# 12V_Regulator.net
KiCad netlist of a schematic drawn in Altium Designer
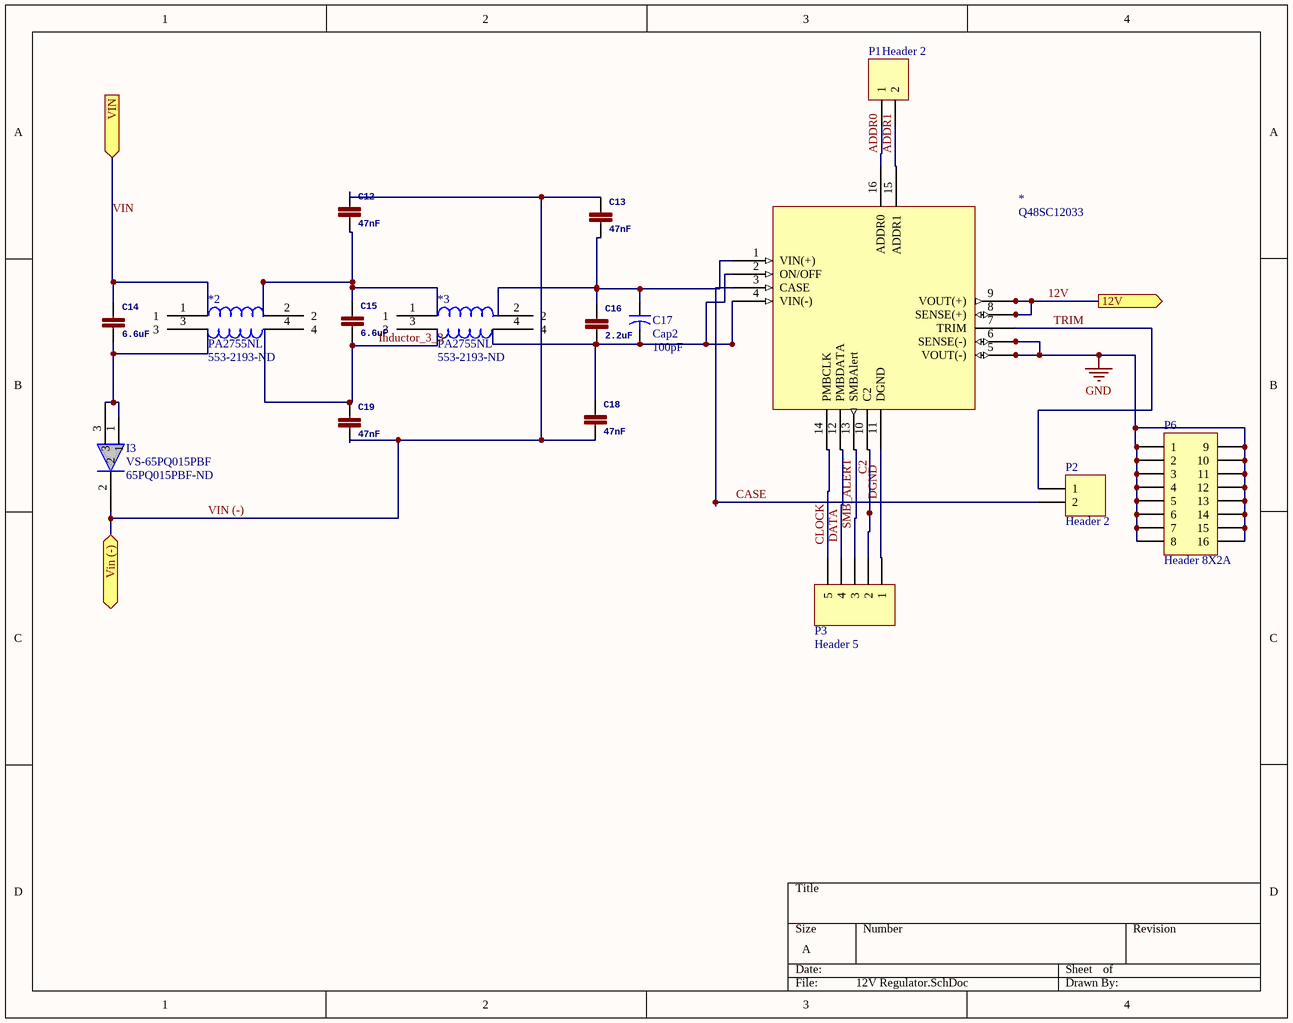
[diagram p0: 12V Regulator.SchDoc]

(export (version "E")
  (design (tool "Eeschema 10.0.6"))
  (components
    (comp (ref "*")
      (value "Q48SC12033")
      (footprint "PCBComponent_1")
      (libsource (lib "Delta_Power_supply") (part "Q48SC12033"))
    )
    (comp (ref "*2")
      (value "PA2755NL")
      (footprint "Makeni")
      (description "COMMON MODE CHOKE 14A 2LN SMD")
      (fields
        (field (name "MANUFACTURER") "Pulse Electronics Power")
        (field (name "SUPPLIER PART NUMBER 1") "553-2193-ND")
      )
      (libsource (lib "Digi_Key") (part "PA2755NL"))
    )
    (comp (ref "*3")
      (value "PA2755NL")
      (footprint "Makeni")
      (description "COMMON MODE CHOKE 14A 2LN SMD")
      (fields
        (field (name "MANUFACTURER") "Pulse Electronics Power")
        (field (name "SUPPLIER PART NUMBER 1") "553-2193-ND")
      )
      (libsource (lib "Digi_Key") (part "PA2755NL"))
    )
    (comp (ref "C12")
      (value "47nF")
      (footprint "0402-CAP")
      (libsource (lib "SparkFun-Retired") (part "2.2UF-CERCAP-07888"))
    )
    (comp (ref "C13")
      (value "47nF")
      (footprint "0402-CAP")
      (libsource (lib "SparkFun-Retired") (part "2.2UF-CERCAP-07888"))
    )
    (comp (ref "C14")
      (value "6.6uF")
      (footprint "1206")
      (libsource (lib "SparkFun-Retired") (part "2.2UF-CERCAP-10009"))
    )
    (comp (ref "C15")
      (value "6.6uF")
      (footprint "1206")
      (libsource (lib "SparkFun-Retired") (part "2.2UF-CERCAP-10009"))
    )
    (comp (ref "C16")
      (value "2.2uF")
      (footprint "0603")
      (libsource (lib "SparkFun-Capacitors") (part "1.5PF-0603-50V-16.667%"))
    )
    (comp (ref "C17")
      (value "Cap2")
      (footprint "CAPR5-4X5")
      (description "Capacitor")
      (fields (field (name "ALTIUM_VALUE") "100pF") (field (name "PUBLISHER") "Altium Limited"))
      (libsource (lib "Miscellaneous Devices") (part "Cap2"))
    )
    (comp (ref "C18")
      (value "47nF")
      (footprint "0402-CAP")
      (libsource (lib "SparkFun-Retired") (part "2.2UF-CERCAP-07888"))
    )
    (comp (ref "C19")
      (value "47nF")
      (footprint "0402-CAP")
      (libsource (lib "SparkFun-Retired") (part "2.2UF-CERCAP-07888"))
    )
    (comp (ref "I3")
      (value "VS-65PQ015PBF")
      (footprint "TO247AC")
      (description "DIODE SCHOTTKY 15V 65A TO247AC")
      (fields
        (field (name "MANUFACTURER") "Vishay Semiconductor Diodes Division")
        (field (name "SUPPLIER PART NUMBER 1") "65PQ015PBF-ND")
      )
      (libsource (lib "Digi_Key") (part "VS-65PQ015PBF"))
    )
    (comp (ref "P1")
      (value "Header 2")
      (footprint "HDR1X2")
      (description "Header, 2-Pin")
      (fields (field (name "PUBLISHER") "Altium Limited"))
      (libsource (lib "Miscellaneous Connectors") (part "Header 2"))
    )
    (comp (ref "P2")
      (value "Header 2")
      (footprint "HDR1X2")
      (description "Header, 2-Pin")
      (fields (field (name "PUBLISHER") "Altium Limited"))
      (libsource (lib "") (part "Header 2_1"))
    )
    (comp (ref "P3")
      (value "Header 5")
      (footprint "HDR1X5")
      (description "Header, 5-Pin")
      (fields (field (name "PUBLISHER") "Altium Limited"))
      (libsource (lib "Miscellaneous Connectors") (part "Header 5"))
    )
    (comp (ref "P6")
      (value "Header 8X2A")
      (footprint "HDR2X8_CEN")
      (description "Header, 8-Pin, Dual row")
      (fields (field (name "PUBLISHER") "Altium Limited"))
      (libsource (lib "Miscellaneous Connectors") (part "Header 8X2A"))
    )
  )
  (nets
    (net (code "1") (name "/12V") (class "Default")
      (node (ref "*") (pin "8") (pinfunction "SENSE(+)_8") (pintype "bidirectional"))
      (node (ref "*") (pin "9") (pinfunction "VOUT(+)_9") (pintype "output"))
    )
    (net (code "2") (name "/ADDR0") (class "Default")
      (node (ref "*") (pin "16") (pinfunction "ADDR0_16") (pintype "passive"))
      (node (ref "P1") (pin "1") (pinfunction "1_1") (pintype "passive"))
    )
    (net (code "3") (name "/ADDR1") (class "Default")
      (node (ref "*") (pin "15") (pinfunction "ADDR1_15") (pintype "passive"))
      (node (ref "P1") (pin "2") (pinfunction "2_2") (pintype "passive"))
    )
    (net (code "5") (name "/CASE") (class "Default")
      (node (ref "*") (pin "3") (pinfunction "CASE_3") (pintype "input"))
      (node (ref "P2") (pin "2") (pinfunction "2_2") (pintype "passive"))
    )
    (net (code "6") (name "/CLOCK") (class "Default")
      (node (ref "*") (pin "14") (pinfunction "PMBCLK_14") (pintype "passive"))
      (node (ref "P3") (pin "5") (pinfunction "5_5") (pintype "passive"))
    )
    (net (code "7") (name "/DATA") (class "Default")
      (node (ref "*") (pin "12") (pinfunction "PMBDATA_12") (pintype "passive"))
      (node (ref "P3") (pin "4") (pinfunction "4_4") (pintype "passive"))
    )
    (net (code "8") (name "/DGND") (class "Default")
      (node (ref "*") (pin "11") (pinfunction "DGND_11") (pintype "passive"))
      (node (ref "P3") (pin "1") (pinfunction "1_1") (pintype "passive"))
    )
    (net (code "9") (name "/Inductor_3_3") (class "Default")
      (node (ref "*2") (pin "4") (pinfunction "4_4") (pintype "passive"))
      (node (ref "*3") (pin "3") (pinfunction "3_3") (pintype "passive"))
      (node (ref "C15") (pin "2") (pinfunction "2_2") (pintype "passive"))
      (node (ref "C19") (pin "1") (pinfunction "1_1") (pintype "passive"))
    )
    (net (code "10") (name "/SMB_ALERT") (class "Default")
      (node (ref "*") (pin "13") (pinfunction "SMBAlert_13") (pintype "output"))
      (node (ref "P3") (pin "3") (pinfunction "3_3") (pintype "passive"))
    )
    (net (code "11") (name "/TRIM") (class "Default")
      (node (ref "*") (pin "7") (pinfunction "TRIM_7") (pintype "passive"))
      (node (ref "P2") (pin "1") (pinfunction "1_1") (pintype "passive"))
    )
    (net (code "12") (name "/VIN") (class "Default")
      (node (ref "*2") (pin "1") (pinfunction "1_1") (pintype "passive"))
      (node (ref "C14") (pin "1") (pinfunction "1_1") (pintype "passive"))
    )
    (net (code "13") (name "/VIN (-)") (class "Default")
      (node (ref "C12") (pin "1") (pinfunction "1_1") (pintype "passive"))
      (node (ref "C13") (pin "1") (pinfunction "1_1") (pintype "passive"))
      (node (ref "C18") (pin "2") (pinfunction "2_2") (pintype "passive"))
      (node (ref "C19") (pin "2") (pinfunction "2_2") (pintype "passive"))
      (node (ref "I3") (pin "2") (pinfunction "2_2") (pintype "passive"))
    )
    (net (code "14") (name "GND") (class "Default")
      (node (ref "*") (pin "5") (pinfunction "VOUT(-)_5") (pintype "bidirectional"))
      (node (ref "*") (pin "6") (pinfunction "SENSE(-)_6") (pintype "bidirectional"))
      (node (ref "P6") (pin "1") (pinfunction "1_1") (pintype "passive"))
      (node (ref "P6") (pin "10") (pinfunction "10_10") (pintype "passive"))
      (node (ref "P6") (pin "11") (pinfunction "11_11") (pintype "passive"))
      (node (ref "P6") (pin "12") (pinfunction "12_12") (pintype "passive"))
      (node (ref "P6") (pin "13") (pinfunction "13_13") (pintype "passive"))
      (node (ref "P6") (pin "14") (pinfunction "14_14") (pintype "passive"))
      (node (ref "P6") (pin "15") (pinfunction "15_15") (pintype "passive"))
      (node (ref "P6") (pin "16") (pinfunction "16_16") (pintype "passive"))
      (node (ref "P6") (pin "2") (pinfunction "2_2") (pintype "passive"))
      (node (ref "P6") (pin "3") (pinfunction "3_3") (pintype "passive"))
      (node (ref "P6") (pin "4") (pinfunction "4_4") (pintype "passive"))
      (node (ref "P6") (pin "5") (pinfunction "5_5") (pintype "passive"))
      (node (ref "P6") (pin "6") (pinfunction "6_6") (pintype "passive"))
      (node (ref "P6") (pin "7") (pinfunction "7_7") (pintype "passive"))
      (node (ref "P6") (pin "8") (pinfunction "8_8") (pintype "passive"))
      (node (ref "P6") (pin "9") (pinfunction "9_9") (pintype "passive"))
    )
    (net (code "15") (name "Net-(*-C2)") (class "Default")
      (node (ref "*") (pin "10") (pinfunction "C2_10") (pintype "passive"))
      (node (ref "P3") (pin "2") (pinfunction "2_2") (pintype "passive"))
    )
    (net (code "16") (name "Net-(*-ON{slash}OFF)") (class "Default")
      (node (ref "*") (pin "2") (pinfunction "ON/OFF_2") (pintype "input"))
      (node (ref "*") (pin "4") (pinfunction "VIN(-)_4") (pintype "input"))
      (node (ref "*3") (pin "4") (pinfunction "4_4") (pintype "passive"))
      (node (ref "C16") (pin "2") (pinfunction "2_2") (pintype "passive"))
      (node (ref "C17") (pin "2") (pinfunction "2_2") (pintype "passive"))
      (node (ref "C18") (pin "1") (pinfunction "1_1") (pintype "passive"))
    )
    (net (code "17") (name "Net-(*-VIN(+))") (class "Default")
      (node (ref "*") (pin "1") (pinfunction "VIN(+)_1") (pintype "input"))
      (node (ref "*3") (pin "2") (pinfunction "2_2") (pintype "passive"))
      (node (ref "C13") (pin "2") (pinfunction "2_2") (pintype "passive"))
      (node (ref "C16") (pin "1") (pinfunction "1_1") (pintype "passive"))
      (node (ref "C17") (pin "1") (pinfunction "1_1") (pintype "passive"))
    )
    (net (code "18") (name "Net-(*2-Pad2)") (class "Default")
      (node (ref "*2") (pin "2") (pinfunction "2_2") (pintype "passive"))
      (node (ref "*3") (pin "1") (pinfunction "1_1") (pintype "passive"))
      (node (ref "C12") (pin "2") (pinfunction "2_2") (pintype "passive"))
      (node (ref "C15") (pin "1") (pinfunction "1_1") (pintype "passive"))
    )
    (net (code "19") (name "Net-(*2-Pad3)") (class "Default")
      (node (ref "*2") (pin "3") (pinfunction "3_3") (pintype "passive"))
      (node (ref "C14") (pin "2") (pinfunction "2_2") (pintype "passive"))
      (node (ref "I3") (pin "1") (pinfunction "1_1") (pintype "passive"))
      (node (ref "I3") (pin "3") (pinfunction "3_3") (pintype "passive"))
    )
  )
)
